# EXP_OBC_COMM.net
KiCad netlist of a schematic drawn in Altium Designer
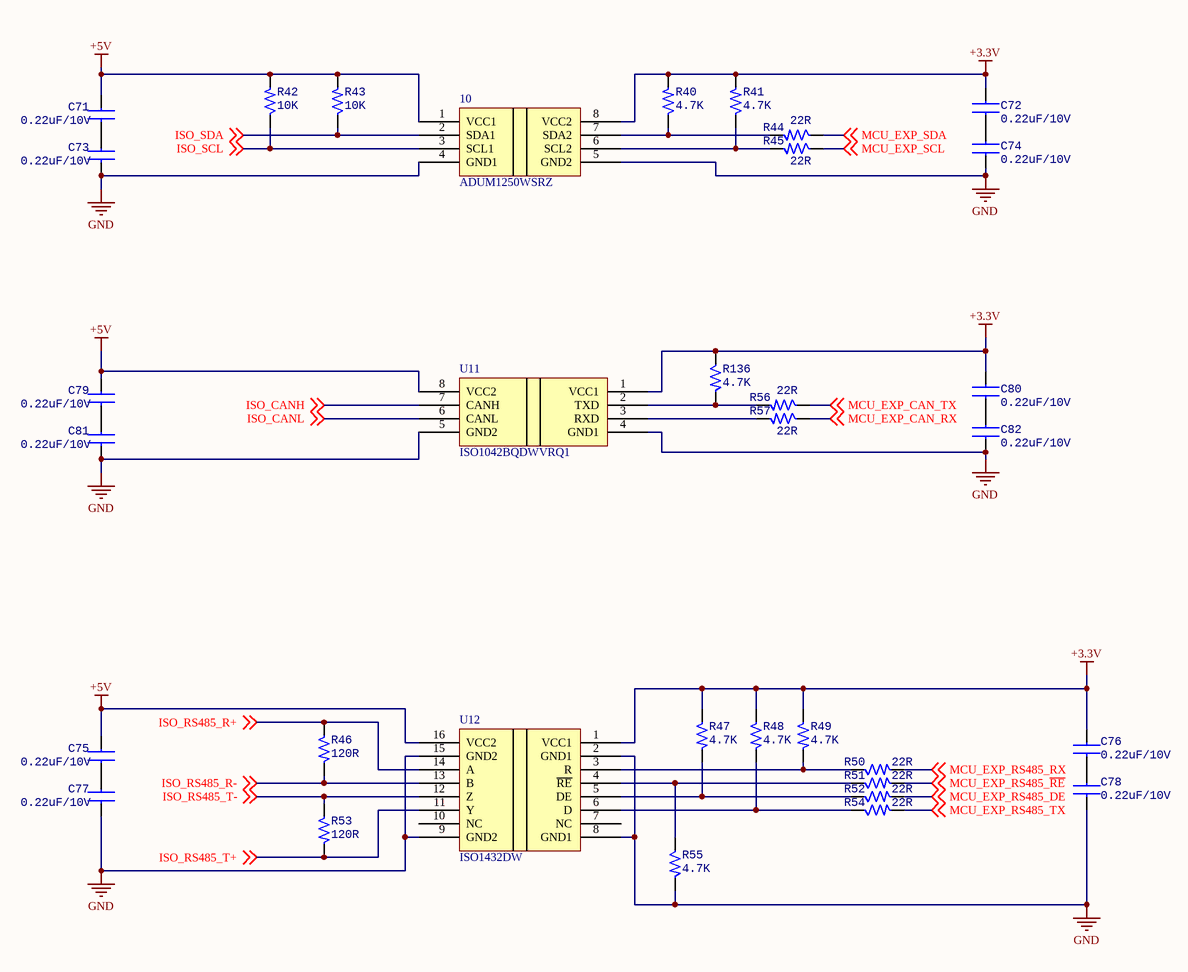
[diagram p0: EXP_OBC_COMM.SchDoc]

(export (version "E")
  (design (tool "Eeschema 10.0.6"))
  (components
    (comp (ref "10")
      (value "ADUM1250WSRZ")
      (footprint "ADUM1250WSRZ")
      (libsource (lib "LAB_B3_209_V1") (part "ADUM1250WSRZ"))
    )
    (comp (ref "C71") (value "0.22uF/10V") (footprint "CAP-CER-0603") (libsource (lib "ID") (part "CAP-CER")))
    (comp (ref "C72") (value "0.22uF/10V") (footprint "CAP-CER-0603") (libsource (lib "ID") (part "CAP-CER")))
    (comp (ref "C73") (value "0.22uF/10V") (footprint "CAP-CER-0603") (libsource (lib "ID") (part "CAP-CER")))
    (comp (ref "C74") (value "0.22uF/10V") (footprint "CAP-CER-0603") (libsource (lib "ID") (part "CAP-CER")))
    (comp (ref "C75") (value "0.22uF/10V") (footprint "CAP-CER-0603") (libsource (lib "ID") (part "CAP-CER")))
    (comp (ref "C76") (value "0.22uF/10V") (footprint "CAP-CER-0603") (libsource (lib "ID") (part "CAP-CER")))
    (comp (ref "C77") (value "0.22uF/10V") (footprint "CAP-CER-0603") (libsource (lib "ID") (part "CAP-CER")))
    (comp (ref "C78") (value "0.22uF/10V") (footprint "CAP-CER-0603") (libsource (lib "ID") (part "CAP-CER")))
    (comp (ref "C79") (value "0.22uF/10V") (footprint "CAP-CER-0603") (libsource (lib "ID") (part "CAP-CER")))
    (comp (ref "C80") (value "0.22uF/10V") (footprint "CAP-CER-0603") (libsource (lib "ID") (part "CAP-CER")))
    (comp (ref "C81") (value "0.22uF/10V") (footprint "CAP-CER-0603") (libsource (lib "ID") (part "CAP-CER")))
    (comp (ref "C82") (value "0.22uF/10V") (footprint "CAP-CER-0603") (libsource (lib "ID") (part "CAP-CER")))
    (comp (ref "R40") (value "4.7K") (footprint "RES-SMD-0603") (libsource (lib "ID") (part "RES-SMD")))
    (comp (ref "R41") (value "4.7K") (footprint "RES-SMD-0603") (libsource (lib "ID") (part "RES-SMD")))
    (comp (ref "R42") (value "10K") (footprint "RES-SMD-0603") (libsource (lib "ID") (part "RES-SMD")))
    (comp (ref "R43") (value "10K") (footprint "RES-SMD-0603") (libsource (lib "ID") (part "RES-SMD")))
    (comp (ref "R44") (value "22R") (footprint "RES-SMD-0603") (libsource (lib "ID") (part "RES-SMD")))
    (comp (ref "R45") (value "22R") (footprint "RES-SMD-0603") (libsource (lib "ID") (part "RES-SMD")))
    (comp (ref "R46") (value "120R") (footprint "RES-SMD-0603") (libsource (lib "ID") (part "RES-SMD")))
    (comp (ref "R47") (value "4.7K") (footprint "RES-SMD-0603") (libsource (lib "ID") (part "RES-SMD")))
    (comp (ref "R48") (value "4.7K") (footprint "RES-SMD-0603") (libsource (lib "ID") (part "RES-SMD")))
    (comp (ref "R49") (value "4.7K") (footprint "RES-SMD-0603") (libsource (lib "ID") (part "RES-SMD")))
    (comp (ref "R50") (value "22R") (footprint "RES-SMD-0603") (libsource (lib "ID") (part "RES-SMD")))
    (comp (ref "R51") (value "22R") (footprint "RES-SMD-0603") (libsource (lib "ID") (part "RES-SMD")))
    (comp (ref "R52") (value "22R") (footprint "RES-SMD-0603") (libsource (lib "ID") (part "RES-SMD")))
    (comp (ref "R53") (value "120R") (footprint "RES-SMD-0603") (libsource (lib "ID") (part "RES-SMD")))
    (comp (ref "R54") (value "22R") (footprint "RES-SMD-0603") (libsource (lib "ID") (part "RES-SMD")))
    (comp (ref "R55") (value "4.7K") (footprint "RES-SMD-0603") (libsource (lib "ID") (part "RES-SMD")))
    (comp (ref "R56") (value "22R") (footprint "RES-SMD-0603") (libsource (lib "ID") (part "RES-SMD")))
    (comp (ref "R57") (value "22R") (footprint "RES-SMD-0603") (libsource (lib "ID") (part "RES-SMD")))
    (comp (ref "R136") (value "4.7K") (footprint "RES-SMD-0603") (libsource (lib "ID") (part "RES-SMD")))
    (comp (ref "U11")
      (value "ISO1042BQDWVRQ1")
      (footprint "ISO1042BQDWVRQ1")
      (libsource (lib "LAB_B3_209_V1") (part "ISO1042BQDWVRQ1"))
    )
    (comp (ref "U12")
      (value "ISO1432DW")
      (footprint "ISO1432DW")
      (libsource (lib "LAB_B3_209_V1") (part "ISO1432DW"))
    )
  )
  (nets
    (net (code "1") (name "+3.3V") (class "Default")
      (node (ref "10") (pin "8") (pinfunction "VCC2_8") (pintype "passive"))
      (node (ref "C72") (pin "2") (pinfunction "2_2") (pintype "passive"))
      (node (ref "C76") (pin "2") (pinfunction "2_2") (pintype "passive"))
      (node (ref "C80") (pin "2") (pinfunction "2_2") (pintype "passive"))
      (node (ref "R136") (pin "1") (pinfunction "1_1") (pintype "passive"))
      (node (ref "R40") (pin "2") (pinfunction "2_2") (pintype "passive"))
      (node (ref "R41") (pin "2") (pinfunction "2_2") (pintype "passive"))
      (node (ref "R47") (pin "1") (pinfunction "1_1") (pintype "passive"))
      (node (ref "R48") (pin "1") (pinfunction "1_1") (pintype "passive"))
      (node (ref "R49") (pin "1") (pinfunction "1_1") (pintype "passive"))
      (node (ref "U11") (pin "1") (pinfunction "VCC1_1") (pintype "passive"))
      (node (ref "U12") (pin "1") (pinfunction "VCC1_1") (pintype "passive"))
    )
    (net (code "2") (name "+5V") (class "Default")
      (node (ref "10") (pin "1") (pinfunction "VCC1_1") (pintype "passive"))
      (node (ref "C71") (pin "2") (pinfunction "2_2") (pintype "passive"))
      (node (ref "C75") (pin "2") (pinfunction "2_2") (pintype "passive"))
      (node (ref "C79") (pin "2") (pinfunction "2_2") (pintype "passive"))
      (node (ref "R42") (pin "2") (pinfunction "2_2") (pintype "passive"))
      (node (ref "R43") (pin "2") (pinfunction "2_2") (pintype "passive"))
      (node (ref "U11") (pin "8") (pinfunction "VCC2_8") (pintype "passive"))
      (node (ref "U12") (pin "16") (pinfunction "VCC2_16") (pintype "passive"))
    )
    (net (code "3") (name "GND") (class "Default")
      (node (ref "10") (pin "4") (pinfunction "GND1_4") (pintype "passive"))
      (node (ref "10") (pin "5") (pinfunction "GND2_5") (pintype "passive"))
      (node (ref "C73") (pin "1") (pinfunction "1_1") (pintype "passive"))
      (node (ref "C74") (pin "1") (pinfunction "1_1") (pintype "passive"))
      (node (ref "C77") (pin "1") (pinfunction "1_1") (pintype "passive"))
      (node (ref "C78") (pin "1") (pinfunction "1_1") (pintype "passive"))
      (node (ref "C81") (pin "1") (pinfunction "1_1") (pintype "passive"))
      (node (ref "C82") (pin "1") (pinfunction "1_1") (pintype "passive"))
      (node (ref "R55") (pin "2") (pinfunction "2_2") (pintype "passive"))
      (node (ref "U11") (pin "4") (pinfunction "GND1_4") (pintype "passive"))
      (node (ref "U11") (pin "5") (pinfunction "GND2_5") (pintype "passive"))
      (node (ref "U12") (pin "15") (pinfunction "GND2_15") (pintype "passive"))
      (node (ref "U12") (pin "2") (pinfunction "GND1_2") (pintype "passive"))
      (node (ref "U12") (pin "8") (pinfunction "GND1_8") (pintype "passive"))
      (node (ref "U12") (pin "9") (pinfunction "GND2_9") (pintype "passive"))
    )
    (net (code "4") (name "ISO_CANH") (class "Default")
      (node (ref "U11") (pin "7") (pinfunction "CANH_7") (pintype "passive"))
    )
    (net (code "5") (name "ISO_CANL") (class "Default")
      (node (ref "U11") (pin "6") (pinfunction "CANL_6") (pintype "passive"))
    )
    (net (code "6") (name "ISO_RS485_R+") (class "Default")
      (node (ref "R46") (pin "1") (pinfunction "1_1") (pintype "passive"))
      (node (ref "U12") (pin "14") (pinfunction "A_14") (pintype "passive"))
    )
    (net (code "7") (name "ISO_RS485_R-") (class "Default")
      (node (ref "R46") (pin "2") (pinfunction "2_2") (pintype "passive"))
      (node (ref "U12") (pin "13") (pinfunction "B_13") (pintype "passive"))
    )
    (net (code "8") (name "ISO_RS485_T+") (class "Default")
      (node (ref "R53") (pin "2") (pinfunction "2_2") (pintype "passive"))
      (node (ref "U12") (pin "11") (pinfunction "Y_11") (pintype "passive"))
    )
    (net (code "9") (name "ISO_RS485_T-") (class "Default")
      (node (ref "R53") (pin "1") (pinfunction "1_1") (pintype "passive"))
      (node (ref "U12") (pin "12") (pinfunction "Z_12") (pintype "passive"))
    )
    (net (code "10") (name "ISO_SCL") (class "Default")
      (node (ref "10") (pin "3") (pinfunction "SCL1_3") (pintype "passive"))
      (node (ref "R42") (pin "1") (pinfunction "1_1") (pintype "passive"))
    )
    (net (code "11") (name "ISO_SDA") (class "Default")
      (node (ref "10") (pin "2") (pinfunction "SDA1_2") (pintype "passive"))
      (node (ref "R43") (pin "1") (pinfunction "1_1") (pintype "passive"))
    )
    (net (code "12") (name "MCU_EXP_CAN_RX") (class "Default")
      (node (ref "R57") (pin "1") (pinfunction "1_1") (pintype "passive"))
    )
    (net (code "13") (name "MCU_EXP_CAN_TX") (class "Default")
      (node (ref "R56") (pin "1") (pinfunction "1_1") (pintype "passive"))
    )
    (net (code "14") (name "MCU_EXP_RS485_DE") (class "Default")
      (node (ref "R52") (pin "2") (pinfunction "2_2") (pintype "passive"))
    )
    (net (code "15") (name "MCU_EXP_RS485_RX") (class "Default")
      (node (ref "R50") (pin "2") (pinfunction "2_2") (pintype "passive"))
    )
    (net (code "16") (name "MCU_EXP_RS485_TX") (class "Default")
      (node (ref "R54") (pin "2") (pinfunction "2_2") (pintype "passive"))
    )
    (net (code "17") (name "MCU_EXP_RS485_~{RE}") (class "Default")
      (node (ref "R51") (pin "2") (pinfunction "2_2") (pintype "passive"))
    )
    (net (code "18") (name "MCU_EXP_SCL") (class "Default")
      (node (ref "R45") (pin "1") (pinfunction "1_1") (pintype "passive"))
    )
    (net (code "19") (name "MCU_EXP_SDA") (class "Default")
      (node (ref "R44") (pin "1") (pinfunction "1_1") (pintype "passive"))
    )
    (net (code "20") (name "Net-(10-SCL2)") (class "Default")
      (node (ref "10") (pin "6") (pinfunction "SCL2_6") (pintype "passive"))
      (node (ref "R41") (pin "1") (pinfunction "1_1") (pintype "passive"))
      (node (ref "R45") (pin "2") (pinfunction "2_2") (pintype "passive"))
    )
    (net (code "21") (name "Net-(10-SDA2)") (class "Default")
      (node (ref "10") (pin "7") (pinfunction "SDA2_7") (pintype "passive"))
      (node (ref "R40") (pin "1") (pinfunction "1_1") (pintype "passive"))
      (node (ref "R44") (pin "2") (pinfunction "2_2") (pintype "passive"))
    )
    (net (code "22") (name "Net-(C71-Pad1)") (class "Default")
      (node (ref "C71") (pin "1") (pinfunction "1_1") (pintype "passive"))
      (node (ref "C73") (pin "2") (pinfunction "2_2") (pintype "passive"))
    )
    (net (code "23") (name "Net-(C72-Pad1)") (class "Default")
      (node (ref "C72") (pin "1") (pinfunction "1_1") (pintype "passive"))
      (node (ref "C74") (pin "2") (pinfunction "2_2") (pintype "passive"))
    )
    (net (code "24") (name "Net-(C75-Pad1)") (class "Default")
      (node (ref "C75") (pin "1") (pinfunction "1_1") (pintype "passive"))
      (node (ref "C77") (pin "2") (pinfunction "2_2") (pintype "passive"))
    )
    (net (code "25") (name "Net-(C76-Pad1)") (class "Default")
      (node (ref "C76") (pin "1") (pinfunction "1_1") (pintype "passive"))
      (node (ref "C78") (pin "2") (pinfunction "2_2") (pintype "passive"))
    )
    (net (code "26") (name "Net-(C79-Pad1)") (class "Default")
      (node (ref "C79") (pin "1") (pinfunction "1_1") (pintype "passive"))
      (node (ref "C81") (pin "2") (pinfunction "2_2") (pintype "passive"))
    )
    (net (code "27") (name "Net-(C80-Pad1)") (class "Default")
      (node (ref "C80") (pin "1") (pinfunction "1_1") (pintype "passive"))
      (node (ref "C82") (pin "2") (pinfunction "2_2") (pintype "passive"))
    )
    (net (code "28") (name "Net-(U11-RXD)") (class "Default")
      (node (ref "R57") (pin "2") (pinfunction "2_2") (pintype "passive"))
      (node (ref "U11") (pin "3") (pinfunction "RXD_3") (pintype "passive"))
    )
    (net (code "29") (name "Net-(U11-TXD)") (class "Default")
      (node (ref "R136") (pin "2") (pinfunction "2_2") (pintype "passive"))
      (node (ref "R56") (pin "2") (pinfunction "2_2") (pintype "passive"))
      (node (ref "U11") (pin "2") (pinfunction "TXD_2") (pintype "passive"))
    )
    (net (code "30") (name "Net-(U12-D)") (class "Default")
      (node (ref "R48") (pin "2") (pinfunction "2_2") (pintype "passive"))
      (node (ref "R54") (pin "1") (pinfunction "1_1") (pintype "passive"))
      (node (ref "U12") (pin "6") (pinfunction "D_6") (pintype "passive"))
    )
    (net (code "31") (name "Net-(U12-DE)") (class "Default")
      (node (ref "R47") (pin "2") (pinfunction "2_2") (pintype "passive"))
      (node (ref "R52") (pin "1") (pinfunction "1_1") (pintype "passive"))
      (node (ref "U12") (pin "5") (pinfunction "DE_5") (pintype "passive"))
    )
    (net (code "32") (name "Net-(U12-R)") (class "Default")
      (node (ref "R49") (pin "2") (pinfunction "2_2") (pintype "passive"))
      (node (ref "R50") (pin "1") (pinfunction "1_1") (pintype "passive"))
      (node (ref "U12") (pin "3") (pinfunction "R_3") (pintype "passive"))
    )
    (net (code "33") (name "Net-(U12-~{RE})") (class "Default")
      (node (ref "R51") (pin "1") (pinfunction "1_1") (pintype "passive"))
      (node (ref "R55") (pin "1") (pinfunction "1_1") (pintype "passive"))
      (node (ref "U12") (pin "4") (pinfunction "~{RE}_4") (pintype "passive"))
    )
    (net (code "34") (name "unconnected-(U12-NC-Pad7)") (class "Default")
      (node (ref "U12") (pin "7") (pinfunction "NC_7") (pintype "passive"))
    )
    (net (code "35") (name "unconnected-(U12-NC-Pad10)") (class "Default")
      (node (ref "U12") (pin "10") (pinfunction "NC_10") (pintype "passive"))
    )
  )
)
